# THMI_2024-07-26.net
KiCad netlist of a schematic drawn in EasyEDA Pro
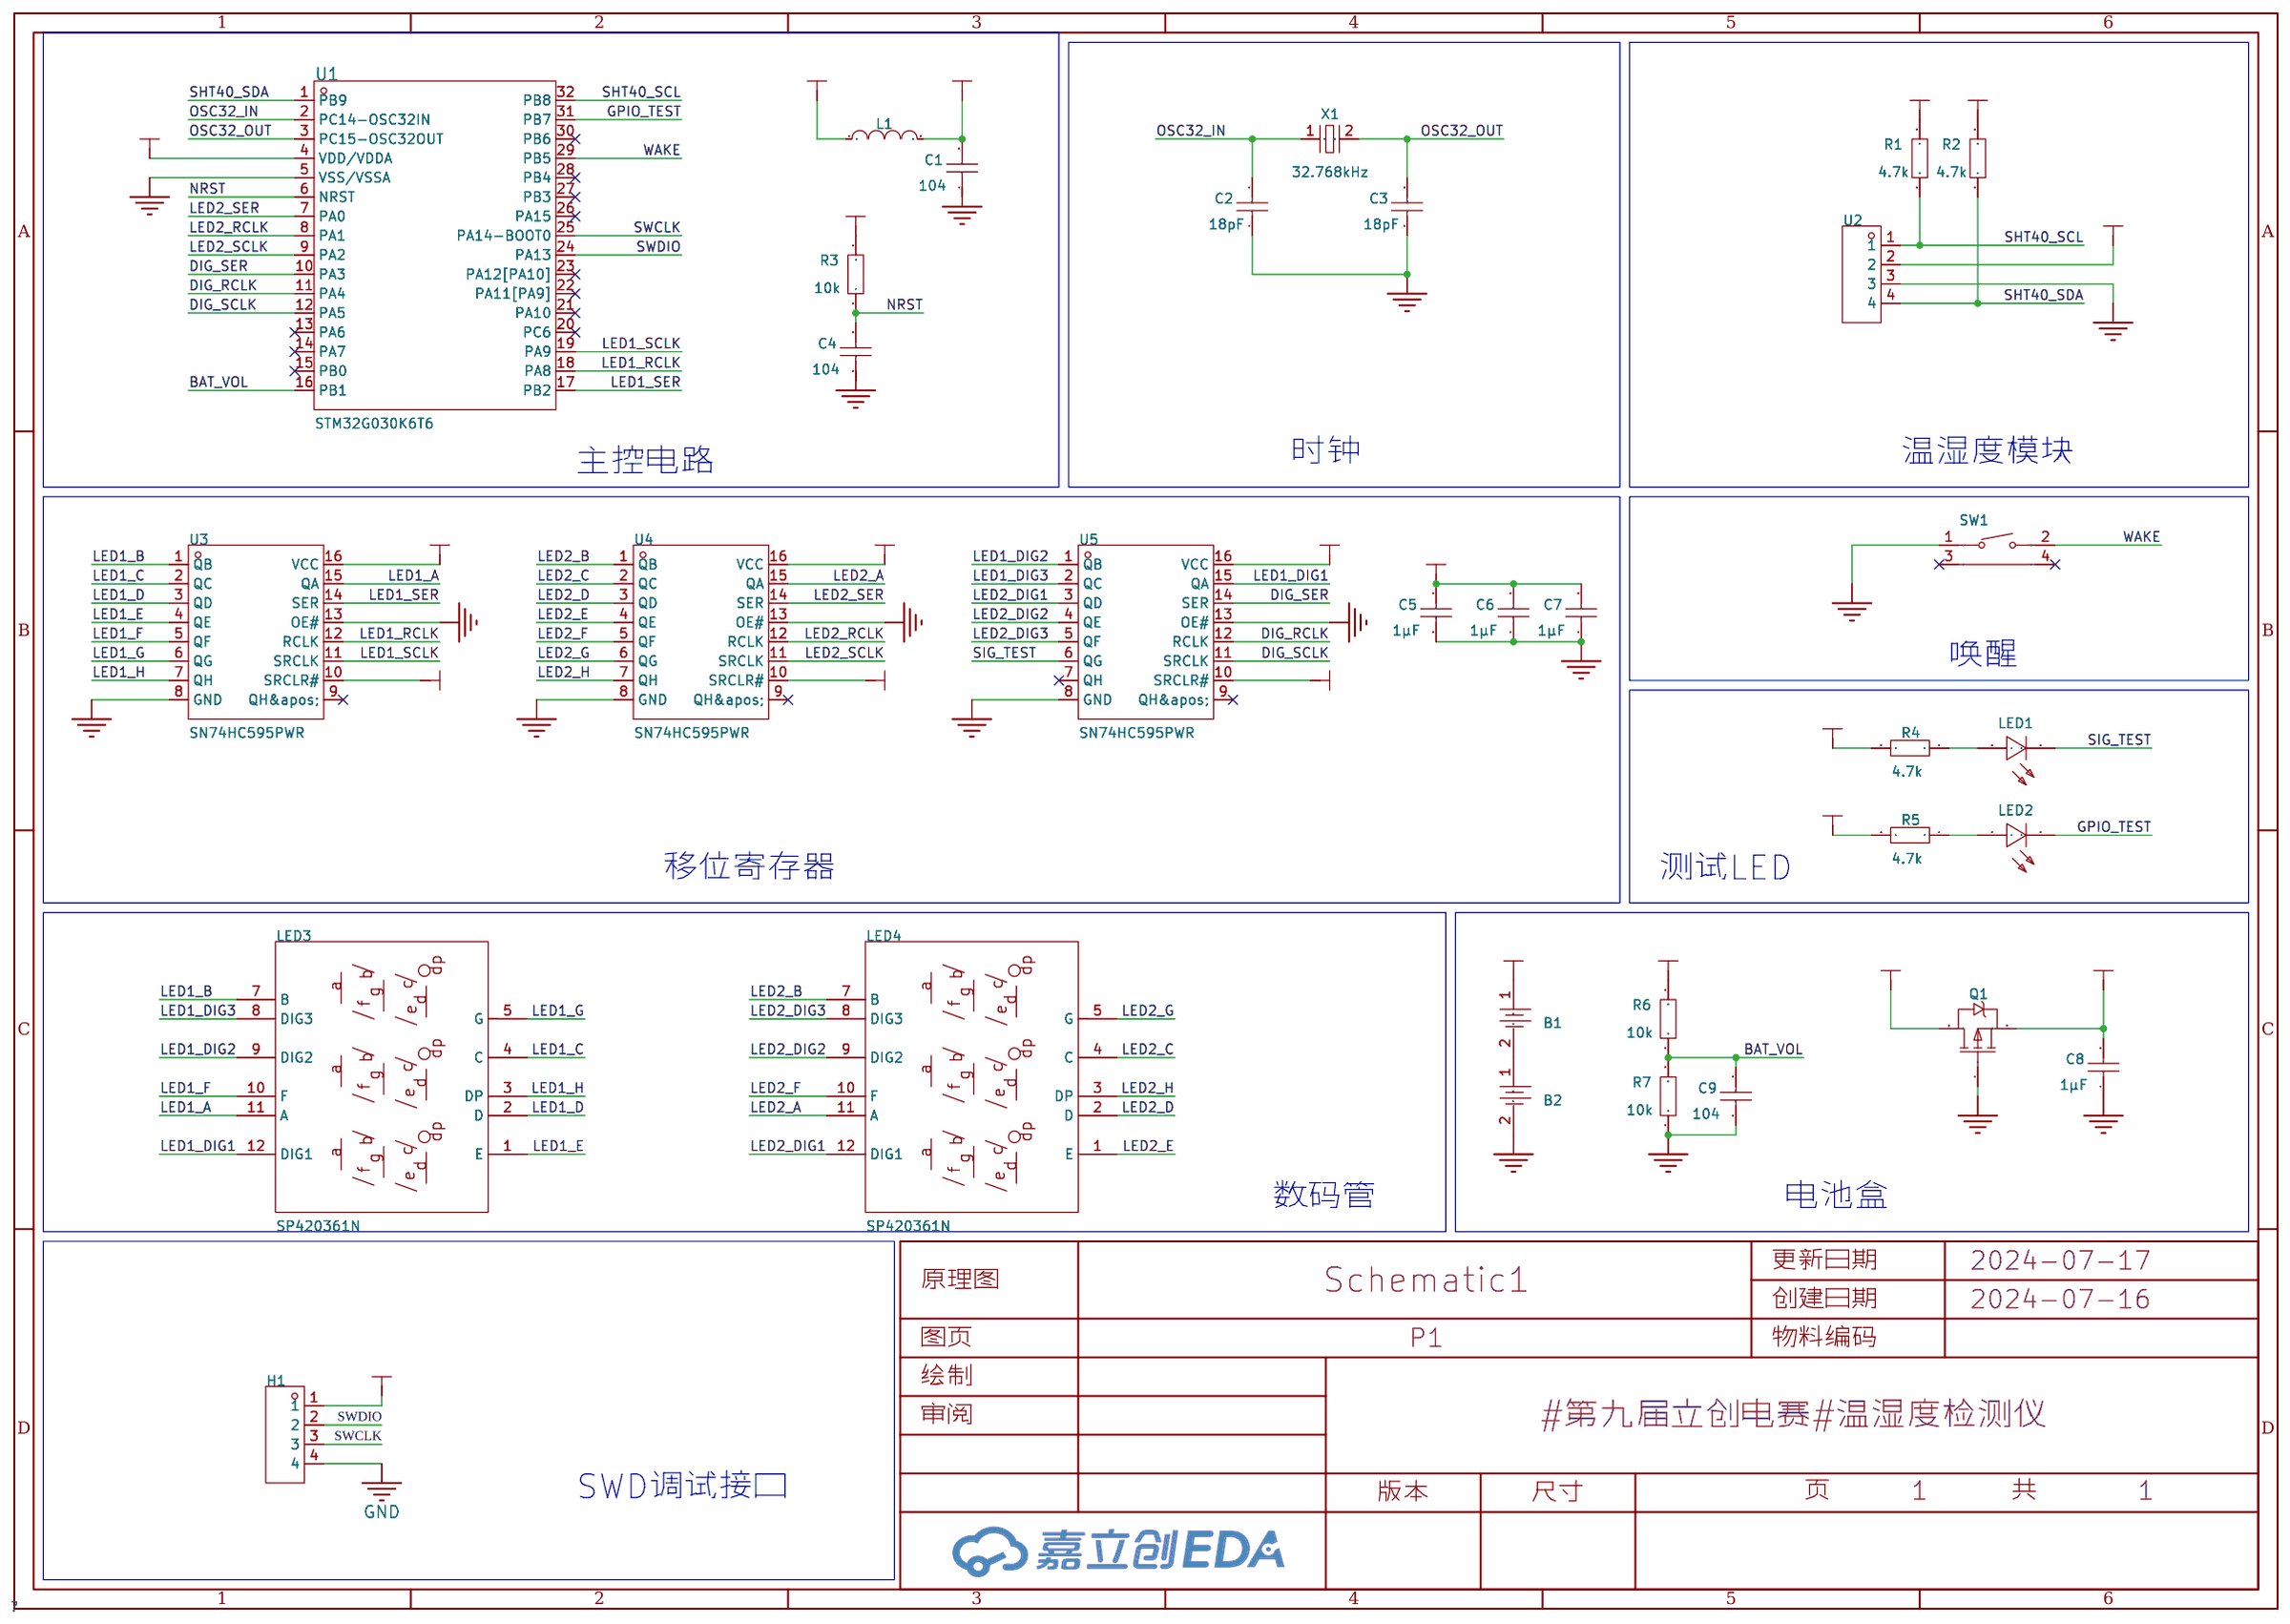
[diagram p0: schematic sheet]

(export (version "E")
  (design (tool "Eeschema 10.0.6"))
  (components
    (comp (ref "B1")
      (value "BH-AA-A5BJ012")
      (footprint "easyedapro:BAT-TH_BH-AA-A5BJ012")
      (description "连接器类型:电池盒;适用电池规格:5号;")
      (fields (field (name "Manufacturer") "MYOUNG(美阳)"))
      (libsource (lib "easyedapro") (part "BH-AA-A5BJ012"))
    )
    (comp (ref "B2")
      (value "BH-AA-A5BJ012")
      (footprint "easyedapro:BAT-TH_BH-AA-A5BJ012")
      (description "连接器类型:电池盒;适用电池规格:5号;")
      (fields (field (name "Manufacturer") "MYOUNG(美阳)"))
      (libsource (lib "easyedapro") (part "BH-AA-A5BJ012"))
    )
    (comp (ref "C1")
      (value "104")
      (footprint "easyedapro:C0603")
      (description "容值:3.3nF;精度:±10%;额定电压:50V;材质(温度系数):X7R;")
      (fields
        (field (name "Manufacturer Part") "CL10B332KB8NNNC")
        (field (name "Manufacturer") "SAMSUNG(三星)")
      )
      (libsource (lib "easyedapro") (part "CL10B332KB8NNNC"))
    )
    (comp (ref "C2")
      (value "18pF")
      (footprint "easyedapro:C0603")
      (description "容值:3.3nF;精度:±10%;额定电压:50V;材质(温度系数):X7R;")
      (fields
        (field (name "Manufacturer Part") "CL10B332KB8NNNC")
        (field (name "Manufacturer") "SAMSUNG(三星)")
      )
      (libsource (lib "easyedapro") (part "CL10B332KB8NNNC"))
    )
    (comp (ref "C3")
      (value "18pF")
      (footprint "easyedapro:C0603")
      (description "容值:3.3nF;精度:±10%;额定电压:50V;材质(温度系数):X7R;")
      (fields
        (field (name "Manufacturer Part") "CL10B332KB8NNNC")
        (field (name "Manufacturer") "SAMSUNG(三星)")
      )
      (libsource (lib "easyedapro") (part "CL10B332KB8NNNC"))
    )
    (comp (ref "C4")
      (value "104")
      (footprint "easyedapro:C0603")
      (description "容值:3.3nF;精度:±10%;额定电压:50V;材质(温度系数):X7R;")
      (fields
        (field (name "Manufacturer Part") "CL10B332KB8NNNC")
        (field (name "Manufacturer") "SAMSUNG(三星)")
      )
      (libsource (lib "easyedapro") (part "CL10B332KB8NNNC"))
    )
    (comp (ref "C5")
      (value "1μF")
      (footprint "easyedapro:C0603")
      (description "容值:3.3nF;精度:±10%;额定电压:50V;材质(温度系数):X7R;")
      (fields
        (field (name "Manufacturer Part") "CL10B332KB8NNNC")
        (field (name "Manufacturer") "SAMSUNG(三星)")
      )
      (libsource (lib "easyedapro") (part "CL10B332KB8NNNC"))
    )
    (comp (ref "C6")
      (value "1μF")
      (footprint "easyedapro:C0603")
      (description "容值:3.3nF;精度:±10%;额定电压:50V;材质(温度系数):X7R;")
      (fields
        (field (name "Manufacturer Part") "CL10B332KB8NNNC")
        (field (name "Manufacturer") "SAMSUNG(三星)")
      )
      (libsource (lib "easyedapro") (part "CL10B332KB8NNNC"))
    )
    (comp (ref "C7")
      (value "1μF")
      (footprint "easyedapro:C0603")
      (description "容值:3.3nF;精度:±10%;额定电压:50V;材质(温度系数):X7R;")
      (fields
        (field (name "Manufacturer Part") "CL10B332KB8NNNC")
        (field (name "Manufacturer") "SAMSUNG(三星)")
      )
      (libsource (lib "easyedapro") (part "CL10B332KB8NNNC"))
    )
    (comp (ref "C8")
      (value "1μF")
      (footprint "easyedapro:C0603")
      (description "容值:3.3nF;精度:±10%;额定电压:50V;材质(温度系数):X7R;")
      (fields
        (field (name "Manufacturer Part") "CL10B332KB8NNNC")
        (field (name "Manufacturer") "SAMSUNG(三星)")
      )
      (libsource (lib "easyedapro") (part "CL10B332KB8NNNC"))
    )
    (comp (ref "C9")
      (value "104")
      (footprint "easyedapro:C0603")
      (description "容值:3.3nF;精度:±10%;额定电压:50V;材质(温度系数):X7R;")
      (fields
        (field (name "Manufacturer Part") "CL10B332KB8NNNC")
        (field (name "Manufacturer") "SAMSUNG(三星)")
      )
      (libsource (lib "easyedapro") (part "CL10B332KB8NNNC"))
    )
    (comp (ref "H1")
      (value "~")
      (footprint "easyedapro:HDR-TH_4P-P2.54-V-F")
      (libsource (lib "easyedapro") (part "2.54-1*4P母"))
    )
    (comp (ref "L1")
      (value "BLM21PG221SN1D")
      (footprint "easyedapro:L0805")
      (description "标称阻抗@测试频率:220Ω@100MHz;误差:±25%;直流电阻(RDC):45mΩ;")
      (fields (field (name "Manufacturer") "muRata(村田)"))
      (libsource (lib "easyedapro") (part "BLM21PG221SN1D"))
    )
    (comp (ref "LED1")
      (value "NCD0603G1")
      (footprint "easyedapro:LED0603-RD")
      (fields (field (name "Manufacturer") "国星光电"))
      (libsource (lib "easyedapro") (part "FC-D1608UGK-520D10"))
    )
    (comp (ref "LED2")
      (value "NCD0603G1")
      (footprint "easyedapro:LED0603-RD")
      (fields (field (name "Manufacturer") "国星光电"))
      (libsource (lib "easyedapro") (part "FC-D1608UGK-520D10"))
    )
    (comp (ref "LED3")
      (value "SP420361N")
      (footprint "easyedapro:LED-SEG-TH_SP420361N")
      (description "数码管位数:3位;发光颜色:红色;LED极性:共阴极;数字/字母大小(英寸):0.36;")
      (fields (field (name "Manufacturer") "ARKLED(方舟)"))
      (libsource (lib "easyedapro") (part "SP420361N"))
    )
    (comp (ref "LED4")
      (value "SP420361N")
      (footprint "easyedapro:LED-SEG-TH_SP420361N")
      (description "数码管位数:3位;发光颜色:红色;LED极性:共阴极;数字/字母大小(英寸):0.36;")
      (fields (field (name "Manufacturer") "ARKLED(方舟)"))
      (libsource (lib "easyedapro") (part "SP420361N"))
    )
    (comp (ref "Q1")
      (value "WST3401")
      (footprint "easyedapro:SOT-23-3_L2.9-W1.6-P1.90-LS2.8-BR")
      (fields (field (name "Manufacturer") "WINSOK(微硕)"))
      (libsource (lib "easyedapro") (part "WST3401"))
    )
    (comp (ref "R1")
      (value "4.7k")
      (footprint "easyedapro:R0603")
      (description "电阻类型:厚膜电阻;阻值:470kΩ;精度:±1%;功率:100mW;最大工作电压:75V;温度系数:±100ppm/°C;")
      (fields
        (field (name "Manufacturer Part") "0603WAF4703T5E")
        (field (name "Manufacturer") "UNI-ROYAL(厚声)")
      )
      (libsource (lib "easyedapro") (part "0603WAF4703T5E"))
    )
    (comp (ref "R2")
      (value "4.7k")
      (footprint "easyedapro:R0603")
      (description "电阻类型:厚膜电阻;阻值:470kΩ;精度:±1%;功率:100mW;最大工作电压:75V;温度系数:±100ppm/°C;")
      (fields
        (field (name "Manufacturer Part") "0603WAF4703T5E")
        (field (name "Manufacturer") "UNI-ROYAL(厚声)")
      )
      (libsource (lib "easyedapro") (part "0603WAF4703T5E"))
    )
    (comp (ref "R3")
      (value "10k")
      (footprint "easyedapro:R0603")
      (description "电阻类型:厚膜电阻;阻值:470kΩ;精度:±1%;功率:100mW;最大工作电压:75V;温度系数:±100ppm/°C;")
      (fields
        (field (name "Manufacturer Part") "0603WAF4703T5E")
        (field (name "Manufacturer") "UNI-ROYAL(厚声)")
      )
      (libsource (lib "easyedapro") (part "0603WAF4703T5E"))
    )
    (comp (ref "R4")
      (value "4.7k")
      (footprint "easyedapro:R0603")
      (description "电阻类型:厚膜电阻;阻值:470kΩ;精度:±1%;功率:100mW;最大工作电压:75V;温度系数:±100ppm/°C;")
      (fields
        (field (name "Manufacturer Part") "0603WAF4703T5E")
        (field (name "Manufacturer") "UNI-ROYAL(厚声)")
      )
      (libsource (lib "easyedapro") (part "0603WAF4703T5E"))
    )
    (comp (ref "R5")
      (value "4.7k")
      (footprint "easyedapro:R0603")
      (description "电阻类型:厚膜电阻;阻值:470kΩ;精度:±1%;功率:100mW;最大工作电压:75V;温度系数:±100ppm/°C;")
      (fields
        (field (name "Manufacturer Part") "0603WAF4703T5E")
        (field (name "Manufacturer") "UNI-ROYAL(厚声)")
      )
      (libsource (lib "easyedapro") (part "0603WAF4703T5E"))
    )
    (comp (ref "R6")
      (value "10k")
      (footprint "easyedapro:R0603")
      (description "电阻类型:厚膜电阻;阻值:470kΩ;精度:±1%;功率:100mW;最大工作电压:75V;温度系数:±100ppm/°C;")
      (fields
        (field (name "Manufacturer Part") "0603WAF4703T5E")
        (field (name "Manufacturer") "UNI-ROYAL(厚声)")
      )
      (libsource (lib "easyedapro") (part "0603WAF4703T5E"))
    )
    (comp (ref "R7")
      (value "10k")
      (footprint "easyedapro:R0603")
      (description "电阻类型:厚膜电阻;阻值:470kΩ;精度:±1%;功率:100mW;最大工作电压:75V;温度系数:±100ppm/°C;")
      (fields
        (field (name "Manufacturer Part") "0603WAF4703T5E")
        (field (name "Manufacturer") "UNI-ROYAL(厚声)")
      )
      (libsource (lib "easyedapro") (part "0603WAF4703T5E"))
    )
    (comp (ref "SW1")
      (value "TS-1010-C-A")
      (footprint "easyedapro:KEY-SMD_TX-1010-X-X")
      (fields (field (name "Manufacturer") "XKB Connectivity(中国星坤)"))
      (libsource (lib "easyedapro") (part "TS-1010-C-A"))
    )
    (comp (ref "U1")
      (value "STM32G030K6T6")
      (footprint "easyedapro:LQFP-32_L7.0-W7.0-P0.80-LS9.0-BL")
      (description "CPU内核:CM0;程序存储容量:32KB;RAM总容量:8KB;GPIO端口数量:30;工作电压范围:2V~3.6V;CPU最大主频:64MHz;程序存储器类型:FLASH;")
      (fields (field (name "Manufacturer") "ST(意法半导体)"))
      (libsource (lib "easyedapro") (part "STM32G030K6T6"))
    )
    (comp (ref "U2")
      (value "X1311FR-04-C43D24")
      (footprint "easyedapro:HDR-TH_4P-P1.27-H-F-W4.5-N")
      (fields (field (name "Manufacturer") "XKB Connectivity(中国星坤)"))
      (libsource (lib "easyedapro") (part "X1311FR-04-C43D24"))
    )
    (comp (ref "U3")
      (value "SN74HC595PWR")
      (footprint "easyedapro:TSSOP-16_L5.0-W4.4-P0.65-LS6.4-BL")
      (description "功能:串行至串行或并行;电源电压:2V~6V;元件数:1;每个元件位数:8;")
      (fields (field (name "Manufacturer") "TI(德州仪器)"))
      (libsource (lib "easyedapro") (part "SN74HC595PWR"))
    )
    (comp (ref "U4")
      (value "SN74HC595PWR")
      (footprint "easyedapro:TSSOP-16_L5.0-W4.4-P0.65-LS6.4-BL")
      (description "功能:串行至串行或并行;电源电压:2V~6V;元件数:1;每个元件位数:8;")
      (fields (field (name "Manufacturer") "TI(德州仪器)"))
      (libsource (lib "easyedapro") (part "SN74HC595PWR"))
    )
    (comp (ref "U5")
      (value "SN74HC595PWR")
      (footprint "easyedapro:TSSOP-16_L5.0-W4.4-P0.65-LS6.4-BL")
      (description "功能:串行至串行或并行;电源电压:2V~6V;元件数:1;每个元件位数:8;")
      (fields (field (name "Manufacturer") "TI(德州仪器)"))
      (libsource (lib "easyedapro") (part "SN74HC595PWR"))
    )
    (comp (ref "X1")
      (value "32.768kHz")
      (footprint "easyedapro:CRYSTAL-SMD_L3.2-W1.5-1")
      (description "晶振类型:贴片晶振;频率:32.768kHz;常温频差:±20ppm;外接负载电容:12.5pF;频率稳定度(全温):±30ppm;")
      (fields (field (name "Manufacturer Part") "H31003271C2070CY") (field (name "Manufacturer") "JGHC(晶光华)"))
      (libsource (lib "easyedapro") (part "H31003271C2070CY"))
    )
  )
  (nets
    (net (code "1") (name "/BAT_VOL") (class "Default")
      (node (ref "C9") (pin "2") (pinfunction "2_2") (pintype "input"))
      (node (ref "R6") (pin "1") (pinfunction "1_1") (pintype "input"))
      (node (ref "R7") (pin "2") (pinfunction "2_2") (pintype "input"))
      (node (ref "U1") (pin "16") (pinfunction "PB1_16") (pintype "input"))
    )
    (net (code "2") (name "/DIG_RCLK") (class "Default")
      (node (ref "U1") (pin "11") (pinfunction "PA4_11") (pintype "input"))
      (node (ref "U5") (pin "12") (pinfunction "RCLK_12") (pintype "unspecified"))
    )
    (net (code "3") (name "/DIG_SCLK") (class "Default")
      (node (ref "U1") (pin "12") (pinfunction "PA5_12") (pintype "input"))
      (node (ref "U5") (pin "11") (pinfunction "SRCLK_11") (pintype "unspecified"))
    )
    (net (code "4") (name "/DIG_SER") (class "Default")
      (node (ref "U1") (pin "10") (pinfunction "PA3_10") (pintype "input"))
      (node (ref "U5") (pin "14") (pinfunction "SER_14") (pintype "unspecified"))
    )
    (net (code "5") (name "/GPIO_TEST") (class "Default")
      (node (ref "LED2") (pin "1") (pinfunction "K_1") (pintype "input"))
      (node (ref "U1") (pin "31") (pinfunction "PB7_31") (pintype "input"))
    )
    (net (code "6") (name "/LED1_A") (class "Default")
      (node (ref "LED3") (pin "11") (pinfunction "A_11") (pintype "input"))
      (node (ref "U3") (pin "15") (pinfunction "QA_15") (pintype "unspecified"))
    )
    (net (code "7") (name "/LED1_B") (class "Default")
      (node (ref "LED3") (pin "7") (pinfunction "B_7") (pintype "input"))
      (node (ref "U3") (pin "1") (pinfunction "QB_1") (pintype "unspecified"))
    )
    (net (code "8") (name "/LED1_C") (class "Default")
      (node (ref "LED3") (pin "4") (pinfunction "C_4") (pintype "input"))
      (node (ref "U3") (pin "2") (pinfunction "QC_2") (pintype "unspecified"))
    )
    (net (code "9") (name "/LED1_D") (class "Default")
      (node (ref "LED3") (pin "2") (pinfunction "D_2") (pintype "input"))
      (node (ref "U3") (pin "3") (pinfunction "QD_3") (pintype "unspecified"))
    )
    (net (code "10") (name "/LED1_DIG1") (class "Default")
      (node (ref "LED3") (pin "12") (pinfunction "DIG1_12") (pintype "input"))
      (node (ref "U5") (pin "15") (pinfunction "QA_15") (pintype "unspecified"))
    )
    (net (code "11") (name "/LED1_DIG2") (class "Default")
      (node (ref "LED3") (pin "9") (pinfunction "DIG2_9") (pintype "input"))
      (node (ref "U5") (pin "1") (pinfunction "QB_1") (pintype "unspecified"))
    )
    (net (code "12") (name "/LED1_DIG3") (class "Default")
      (node (ref "LED3") (pin "8") (pinfunction "DIG3_8") (pintype "input"))
      (node (ref "U5") (pin "2") (pinfunction "QC_2") (pintype "unspecified"))
    )
    (net (code "13") (name "/LED1_E") (class "Default")
      (node (ref "LED3") (pin "1") (pinfunction "E_1") (pintype "input"))
      (node (ref "U3") (pin "4") (pinfunction "QE_4") (pintype "unspecified"))
    )
    (net (code "14") (name "/LED1_F") (class "Default")
      (node (ref "LED3") (pin "10") (pinfunction "F_10") (pintype "input"))
      (node (ref "U3") (pin "5") (pinfunction "QF_5") (pintype "unspecified"))
    )
    (net (code "15") (name "/LED1_G") (class "Default")
      (node (ref "LED3") (pin "5") (pinfunction "G_5") (pintype "input"))
      (node (ref "U3") (pin "6") (pinfunction "QG_6") (pintype "unspecified"))
    )
    (net (code "16") (name "/LED1_H") (class "Default")
      (node (ref "LED3") (pin "3") (pinfunction "DP_3") (pintype "input"))
      (node (ref "U3") (pin "7") (pinfunction "QH_7") (pintype "unspecified"))
    )
    (net (code "17") (name "/LED1_RCLK") (class "Default")
      (node (ref "U1") (pin "18") (pinfunction "PA8_18") (pintype "input"))
      (node (ref "U3") (pin "12") (pinfunction "RCLK_12") (pintype "unspecified"))
    )
    (net (code "18") (name "/LED1_SCLK") (class "Default")
      (node (ref "U1") (pin "19") (pinfunction "PA9_19") (pintype "input"))
      (node (ref "U3") (pin "11") (pinfunction "SRCLK_11") (pintype "unspecified"))
    )
    (net (code "19") (name "/LED1_SER") (class "Default")
      (node (ref "U1") (pin "17") (pinfunction "PB2_17") (pintype "input"))
      (node (ref "U3") (pin "14") (pinfunction "SER_14") (pintype "unspecified"))
    )
    (net (code "20") (name "/LED2_A") (class "Default")
      (node (ref "LED4") (pin "11") (pinfunction "A_11") (pintype "input"))
      (node (ref "U4") (pin "15") (pinfunction "QA_15") (pintype "unspecified"))
    )
    (net (code "21") (name "/LED2_B") (class "Default")
      (node (ref "LED4") (pin "7") (pinfunction "B_7") (pintype "input"))
      (node (ref "U4") (pin "1") (pinfunction "QB_1") (pintype "unspecified"))
    )
    (net (code "22") (name "/LED2_C") (class "Default")
      (node (ref "LED4") (pin "4") (pinfunction "C_4") (pintype "input"))
      (node (ref "U4") (pin "2") (pinfunction "QC_2") (pintype "unspecified"))
    )
    (net (code "23") (name "/LED2_D") (class "Default")
      (node (ref "LED4") (pin "2") (pinfunction "D_2") (pintype "input"))
      (node (ref "U4") (pin "3") (pinfunction "QD_3") (pintype "unspecified"))
    )
    (net (code "24") (name "/LED2_DIG1") (class "Default")
      (node (ref "LED4") (pin "12") (pinfunction "DIG1_12") (pintype "input"))
      (node (ref "U5") (pin "3") (pinfunction "QD_3") (pintype "unspecified"))
    )
    (net (code "25") (name "/LED2_DIG2") (class "Default")
      (node (ref "LED4") (pin "9") (pinfunction "DIG2_9") (pintype "input"))
      (node (ref "U5") (pin "4") (pinfunction "QE_4") (pintype "unspecified"))
    )
    (net (code "26") (name "/LED2_DIG3") (class "Default")
      (node (ref "LED4") (pin "8") (pinfunction "DIG3_8") (pintype "input"))
      (node (ref "U5") (pin "5") (pinfunction "QF_5") (pintype "unspecified"))
    )
    (net (code "27") (name "/LED2_E") (class "Default")
      (node (ref "LED4") (pin "1") (pinfunction "E_1") (pintype "input"))
      (node (ref "U4") (pin "4") (pinfunction "QE_4") (pintype "unspecified"))
    )
    (net (code "28") (name "/LED2_F") (class "Default")
      (node (ref "LED4") (pin "10") (pinfunction "F_10") (pintype "input"))
      (node (ref "U4") (pin "5") (pinfunction "QF_5") (pintype "unspecified"))
    )
    (net (code "29") (name "/LED2_G") (class "Default")
      (node (ref "LED4") (pin "5") (pinfunction "G_5") (pintype "input"))
      (node (ref "U4") (pin "6") (pinfunction "QG_6") (pintype "unspecified"))
    )
    (net (code "30") (name "/LED2_H") (class "Default")
      (node (ref "LED4") (pin "3") (pinfunction "DP_3") (pintype "input"))
      (node (ref "U4") (pin "7") (pinfunction "QH_7") (pintype "unspecified"))
    )
    (net (code "31") (name "/LED2_RCLK") (class "Default")
      (node (ref "U1") (pin "8") (pinfunction "PA1_8") (pintype "input"))
      (node (ref "U4") (pin "12") (pinfunction "RCLK_12") (pintype "unspecified"))
    )
    (net (code "32") (name "/LED2_SCLK") (class "Default")
      (node (ref "U1") (pin "9") (pinfunction "PA2_9") (pintype "input"))
      (node (ref "U4") (pin "11") (pinfunction "SRCLK_11") (pintype "unspecified"))
    )
    (net (code "33") (name "/LED2_SER") (class "Default")
      (node (ref "U1") (pin "7") (pinfunction "PA0_7") (pintype "input"))
      (node (ref "U4") (pin "14") (pinfunction "SER_14") (pintype "unspecified"))
    )
    (net (code "34") (name "/NRST") (class "Default")
      (node (ref "C4") (pin "2") (pinfunction "2_2") (pintype "input"))
      (node (ref "R3") (pin "1") (pinfunction "1_1") (pintype "input"))
      (node (ref "U1") (pin "6") (pinfunction "NRST_6") (pintype "input"))
    )
    (net (code "35") (name "/OSC32_IN") (class "Default")
      (node (ref "C2") (pin "2") (pinfunction "2_2") (pintype "input"))
      (node (ref "U1") (pin "2") (pinfunction "PC14-OSC32IN_2") (pintype "input"))
      (node (ref "X1") (pin "1") (pinfunction "1_1") (pintype "input"))
    )
    (net (code "36") (name "/OSC32_OUT") (class "Default")
      (node (ref "C3") (pin "2") (pinfunction "2_2") (pintype "input"))
      (node (ref "U1") (pin "3") (pinfunction "PC15-OSC32OUT_3") (pintype "input"))
      (node (ref "X1") (pin "2") (pinfunction "GND_2") (pintype "input"))
    )
    (net (code "37") (name "/SHT40_SCL") (class "Default")
      (node (ref "R1") (pin "1") (pinfunction "1_1") (pintype "input"))
      (node (ref "U1") (pin "32") (pinfunction "PB8_32") (pintype "input"))
      (node (ref "U2") (pin "1") (pinfunction "1_1") (pintype "unspecified"))
    )
    (net (code "38") (name "/SHT40_SDA") (class "Default")
      (node (ref "R2") (pin "1") (pinfunction "1_1") (pintype "input"))
      (node (ref "U1") (pin "1") (pinfunction "PB9_1") (pintype "input"))
      (node (ref "U2") (pin "4") (pinfunction "4_4") (pintype "unspecified"))
    )
    (net (code "39") (name "/SIG_TEST") (class "Default")
      (node (ref "LED1") (pin "1") (pinfunction "K_1") (pintype "input"))
      (node (ref "U5") (pin "6") (pinfunction "QG_6") (pintype "unspecified"))
    )
    (net (code "40") (name "/SWCLK") (class "Default")
      (node (ref "H1") (pin "3") (pinfunction "3_3") (pintype "unspecified"))
      (node (ref "U1") (pin "25") (pinfunction "PA14-BOOT0_25") (pintype "input"))
    )
    (net (code "41") (name "/SWDIO") (class "Default")
      (node (ref "H1") (pin "2") (pinfunction "2_2") (pintype "unspecified"))
      (node (ref "U1") (pin "24") (pinfunction "PA13_24") (pintype "input"))
    )
    (net (code "42") (name "/WAKE") (class "Default")
      (node (ref "SW1") (pin "2") (pinfunction "2_2") (pintype "unspecified"))
      (node (ref "U1") (pin "29") (pinfunction "PB5_29") (pintype "input"))
    )
    (net (code "43") (name "3V") (class "Default")
      (node (ref "C5") (pin "2") (pinfunction "2_2") (pintype "input"))
      (node (ref "C6") (pin "2") (pinfunction "2_2") (pintype "input"))
      (node (ref "C7") (pin "2") (pinfunction "2_2") (pintype "input"))
      (node (ref "C8") (pin "2") (pinfunction "2_2") (pintype "input"))
      (node (ref "H1") (pin "1") (pinfunction "1_1") (pintype "unspecified"))
      (node (ref "L1") (pin "1") (pinfunction "1_1") (pintype "input"))
      (node (ref "Q1") (pin "2") (pinfunction "S_2") (pintype "unspecified"))
      (node (ref "R1") (pin "2") (pinfunction "2_2") (pintype "input"))
      (node (ref "R2") (pin "2") (pinfunction "2_2") (pintype "input"))
      (node (ref "R3") (pin "2") (pinfunction "2_2") (pintype "input"))
      (node (ref "R4") (pin "2") (pinfunction "2_2") (pintype "input"))
      (node (ref "R5") (pin "2") (pinfunction "2_2") (pintype "input"))
      (node (ref "R6") (pin "2") (pinfunction "2_2") (pintype "input"))
      (node (ref "U2") (pin "2") (pinfunction "2_2") (pintype "unspecified"))
      (node (ref "U3") (pin "10") (pinfunction "SRCLR#_10") (pintype "unspecified"))
      (node (ref "U3") (pin "16") (pinfunction "VCC_16") (pintype "unspecified"))
      (node (ref "U4") (pin "10") (pinfunction "SRCLR#_10") (pintype "unspecified"))
      (node (ref "U4") (pin "16") (pinfunction "VCC_16") (pintype "unspecified"))
      (node (ref "U5") (pin "10") (pinfunction "SRCLR#_10") (pintype "unspecified"))
      (node (ref "U5") (pin "16") (pinfunction "VCC_16") (pintype "unspecified"))
    )
    (net (code "44") (name "GND") (class "Default")
      (node (ref "B2") (pin "2") (pinfunction "2_2") (pintype "input"))
      (node (ref "C1") (pin "1") (pinfunction "1_1") (pintype "input"))
      (node (ref "C2") (pin "1") (pinfunction "1_1") (pintype "input"))
      (node (ref "C3") (pin "1") (pinfunction "1_1") (pintype "input"))
      (node (ref "C4") (pin "1") (pinfunction "1_1") (pintype "input"))
      (node (ref "C5") (pin "1") (pinfunction "1_1") (pintype "input"))
      (node (ref "C6") (pin "1") (pinfunction "1_1") (pintype "input"))
      (node (ref "C7") (pin "1") (pinfunction "1_1") (pintype "input"))
      (node (ref "C8") (pin "1") (pinfunction "1_1") (pintype "input"))
      (node (ref "C9") (pin "1") (pinfunction "1_1") (pintype "input"))
      (node (ref "H1") (pin "4") (pinfunction "4_4") (pintype "unspecified"))
      (node (ref "Q1") (pin "1") (pinfunction "G_1") (pintype "unspecified"))
      (node (ref "R7") (pin "1") (pinfunction "1_1") (pintype "input"))
      (node (ref "SW1") (pin "1") (pinfunction "1_1") (pintype "unspecified"))
      (node (ref "U1") (pin "5") (pinfunction "VSS/VSSA_5") (pintype "input"))
      (node (ref "U2") (pin "3") (pinfunction "3_3") (pintype "unspecified"))
      (node (ref "U3") (pin "13") (pinfunction "OE#_13") (pintype "unspecified"))
      (node (ref "U3") (pin "8") (pinfunction "GND_8") (pintype "unspecified"))
      (node (ref "U4") (pin "13") (pinfunction "OE#_13") (pintype "unspecified"))
      (node (ref "U4") (pin "8") (pinfunction "GND_8") (pintype "unspecified"))
      (node (ref "U5") (pin "13") (pinfunction "OE#_13") (pintype "unspecified"))
      (node (ref "U5") (pin "8") (pinfunction "GND_8") (pintype "unspecified"))
    )
    (net (code "45") (name "Net-(B1-Pad2)") (class "Default")
      (node (ref "B1") (pin "2") (pinfunction "2_2") (pintype "input"))
      (node (ref "B2") (pin "1") (pinfunction "1_1") (pintype "input"))
    )
    (net (code "46") (name "Net-(LED1-A)") (class "Default")
      (node (ref "LED1") (pin "2") (pinfunction "A_2") (pintype "input"))
      (node (ref "R4") (pin "1") (pinfunction "1_1") (pintype "input"))
    )
    (net (code "47") (name "Net-(LED2-A)") (class "Default")
      (node (ref "LED2") (pin "2") (pinfunction "A_2") (pintype "input"))
      (node (ref "R5") (pin "1") (pinfunction "1_1") (pintype "input"))
    )
    (net (code "48") (name "VBAT") (class "Default")
      (node (ref "B1") (pin "1") (pinfunction "1_1") (pintype "input"))
      (node (ref "Q1") (pin "3") (pinfunction "D_3") (pintype "unspecified"))
    )
    (net (code "49") (name "VDD") (class "Default")
      (node (ref "C1") (pin "2") (pinfunction "2_2") (pintype "input"))
      (node (ref "L1") (pin "2") (pinfunction "2_2") (pintype "input"))
      (node (ref "U1") (pin "4") (pinfunction "VDD/VDDA_4") (pintype "input"))
    )
    (net (code "50") (name "unconnected-(SW1-Pad3)") (class "Default")
      (node (ref "SW1") (pin "3") (pinfunction "3_3") (pintype "unspecified+no_connect"))
    )
    (net (code "51") (name "unconnected-(SW1-Pad4)") (class "Default")
      (node (ref "SW1") (pin "4") (pinfunction "4_4") (pintype "unspecified+no_connect"))
    )
    (net (code "52") (name "unconnected-(U1-PA6-Pad13)") (class "Default")
      (node (ref "U1") (pin "13") (pinfunction "PA6_13") (pintype "input+no_connect"))
    )
    (net (code "53") (name "unconnected-(U1-PA7-Pad14)") (class "Default")
      (node (ref "U1") (pin "14") (pinfunction "PA7_14") (pintype "input+no_connect"))
    )
    (net (code "54") (name "unconnected-(U1-PA10-Pad21)") (class "Default")
      (node (ref "U1") (pin "21") (pinfunction "PA10_21") (pintype "input+no_connect"))
    )
    (net (code "55") (name "unconnected-(U1-PA11[PA9]-Pad22)") (class "Default")
      (node (ref "U1") (pin "22") (pinfunction "PA11[PA9]_22") (pintype "input+no_connect"))
    )
    (net (code "56") (name "unconnected-(U1-PA12[PA10]-Pad23)") (class "Default")
      (node (ref "U1") (pin "23") (pinfunction "PA12[PA10]_23") (pintype "input+no_connect"))
    )
    (net (code "57") (name "unconnected-(U1-PA15-Pad26)") (class "Default")
      (node (ref "U1") (pin "26") (pinfunction "PA15_26") (pintype "input+no_connect"))
    )
    (net (code "58") (name "unconnected-(U1-PB0-Pad15)") (class "Default")
      (node (ref "U1") (pin "15") (pinfunction "PB0_15") (pintype "input+no_connect"))
    )
    (net (code "59") (name "unconnected-(U1-PB3-Pad27)") (class "Default")
      (node (ref "U1") (pin "27") (pinfunction "PB3_27") (pintype "input+no_connect"))
    )
    (net (code "60") (name "unconnected-(U1-PB4-Pad28)") (class "Default")
      (node (ref "U1") (pin "28") (pinfunction "PB4_28") (pintype "input+no_connect"))
    )
    (net (code "61") (name "unconnected-(U1-PB6-Pad30)") (class "Default")
      (node (ref "U1") (pin "30") (pinfunction "PB6_30") (pintype "input+no_connect"))
    )
    (net (code "62") (name "unconnected-(U1-PC6-Pad20)") (class "Default")
      (node (ref "U1") (pin "20") (pinfunction "PC6_20") (pintype "input+no_connect"))
    )
    (net (code "63") (name "unconnected-(U3-QH&apos;-Pad9)") (class "Default")
      (node (ref "U3") (pin "9") (pinfunction "QH&apos;_9") (pintype "unspecified+no_connect"))
    )
    (net (code "64") (name "unconnected-(U4-QH&apos;-Pad9)") (class "Default")
      (node (ref "U4") (pin "9") (pinfunction "QH&apos;_9") (pintype "unspecified+no_connect"))
    )
    (net (code "65") (name "unconnected-(U5-QH&apos;-Pad9)") (class "Default")
      (node (ref "U5") (pin "9") (pinfunction "QH&apos;_9") (pintype "unspecified+no_connect"))
    )
    (net (code "66") (name "unconnected-(U5-QH-Pad7)") (class "Default")
      (node (ref "U5") (pin "7") (pinfunction "QH_7") (pintype "unspecified+no_connect"))
    )
  )
)
